# etapa_5.net
KiCad netlist of a schematic drawn in EAGLE
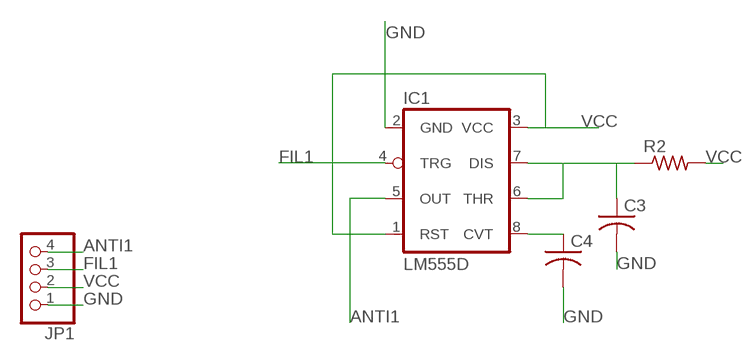
[diagram p0: schematic, sheet 1]

(export (version "E")
  (design (tool "Eeschema 10.0.6"))
  (components
    (comp (ref "C3")
      (value "C-USC0603")
      (footprint "eagle-import:C0603")
      (libsource (lib "eagle-import") (part "C-USC0603"))
    )
    (comp (ref "C4")
      (value "C-USC0603")
      (footprint "eagle-import:C0603")
      (libsource (lib "eagle-import") (part "C-USC0603"))
    )
    (comp (ref "IC1")
      (value "LM555D")
      (footprint "eagle-import:SO08")
      (libsource (lib "eagle-import") (part "555DLM"))
    )
    (comp (ref "JP1")
      (value "PINHD-1X4")
      (footprint "eagle-import:1X04")
      (libsource (lib "eagle-import") (part "PINHD-1X4"))
    )
    (comp (ref "R2")
      (value "R-US_R0603")
      (footprint "eagle-import:R0603")
      (libsource (lib "eagle-import") (part "R-US_R0603"))
    )
  )
  (nets
    (net (code "1") (name "/ANTI1") (class "Default")
      (node (ref "IC1") (pin "5") (pinfunction "OUT_5") (pintype "input"))
      (node (ref "JP1") (pin "4") (pinfunction "4_4") (pintype "passive"))
    )
    (net (code "2") (name "/FIL1") (class "Default")
      (node (ref "IC1") (pin "4") (pinfunction "TRG_4") (pintype "input"))
      (node (ref "JP1") (pin "3") (pinfunction "3_3") (pintype "passive"))
    )
    (net (code "3") (name "/GND") (class "Default")
      (node (ref "C3") (pin "2") (pinfunction "2_2") (pintype "passive"))
      (node (ref "C4") (pin "2") (pinfunction "2_2") (pintype "passive"))
      (node (ref "IC1") (pin "2") (pinfunction "GND_2") (pintype "input"))
      (node (ref "JP1") (pin "1") (pinfunction "1_1") (pintype "passive"))
    )
    (net (code "4") (name "/VCC") (class "Default")
      (node (ref "IC1") (pin "1") (pinfunction "RST_1") (pintype "power_in"))
      (node (ref "IC1") (pin "3") (pinfunction "VCC_3") (pintype "output"))
      (node (ref "JP1") (pin "2") (pinfunction "2_2") (pintype "passive"))
      (node (ref "R2") (pin "2") (pinfunction "2_2") (pintype "passive"))
    )
    (net (code "5") (name "Net-(IC1-CVT)") (class "Default")
      (node (ref "C4") (pin "1") (pinfunction "1_1") (pintype "passive"))
      (node (ref "IC1") (pin "8") (pinfunction "CVT_8") (pintype "power_in"))
    )
    (net (code "6") (name "Net-(IC1-DIS)") (class "Default")
      (node (ref "C3") (pin "1") (pinfunction "1_1") (pintype "passive"))
      (node (ref "IC1") (pin "6") (pinfunction "THR_6") (pintype "input"))
      (node (ref "IC1") (pin "7") (pinfunction "DIS_7") (pintype "input"))
      (node (ref "R2") (pin "1") (pinfunction "1_1") (pintype "passive"))
    )
  )
)
